# Clock.net
KiCad netlist of a schematic drawn in Altium Designer
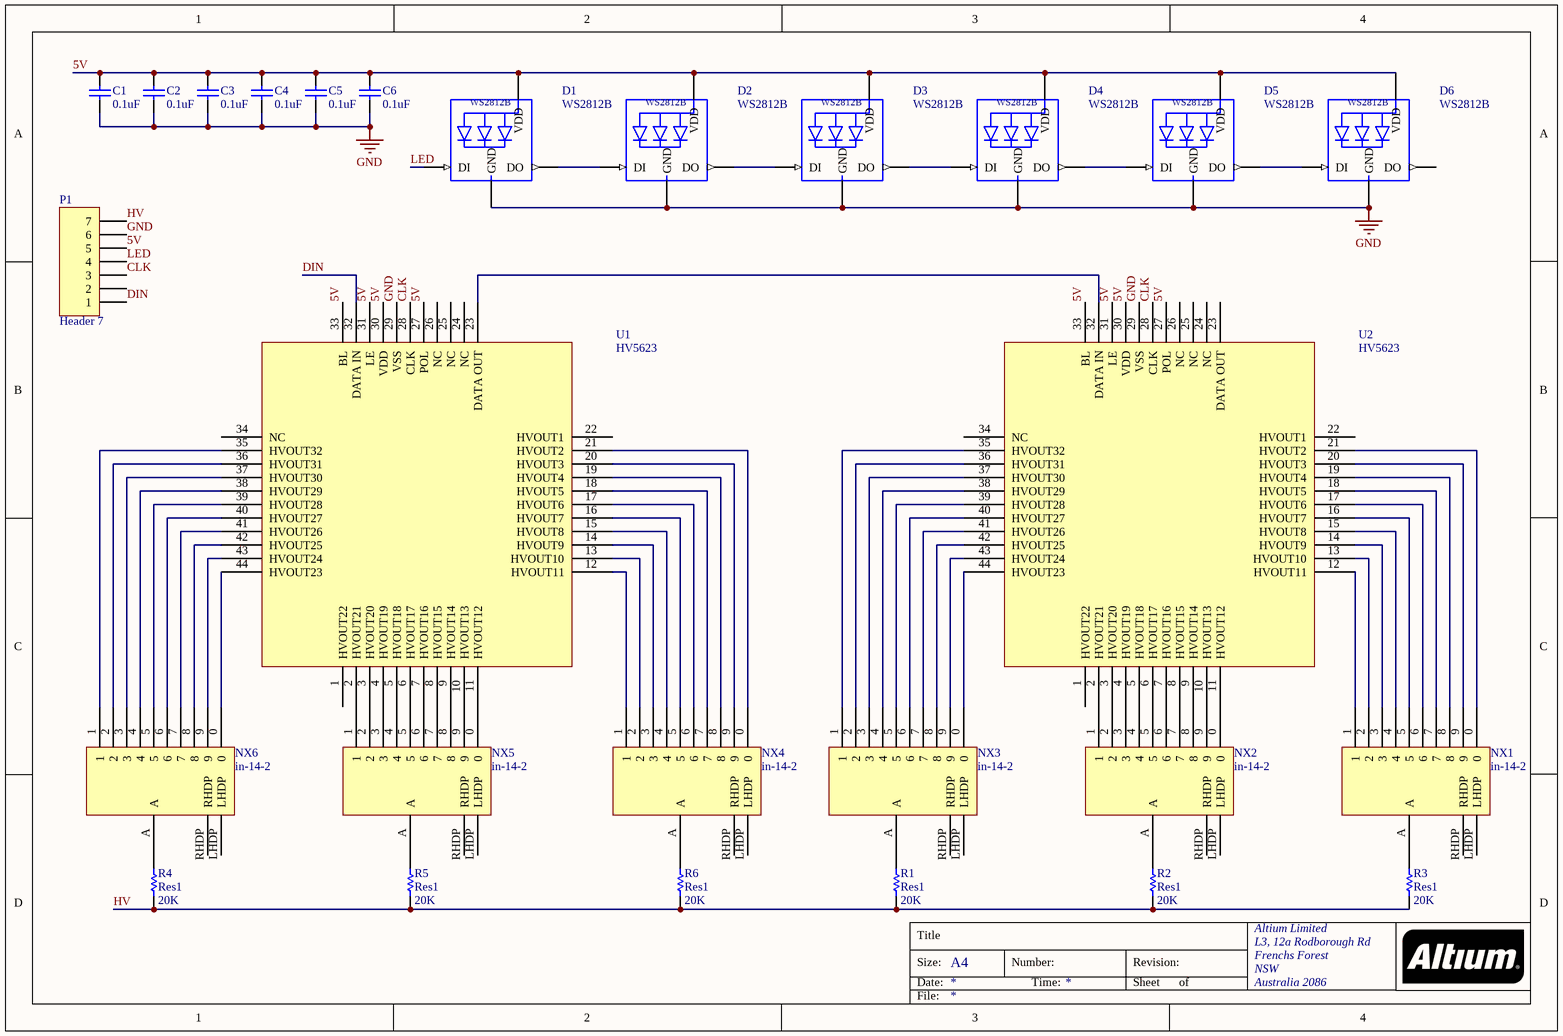
[diagram p0: Clock.SchDoc]

(export (version "E")
  (design (tool "Eeschema 10.0.6"))
  (components
    (comp (ref "C1")
      (value "0.1uF")
      (footprint "1608[0603]")
      (description "Capacitor")
      (fields (field (name "PUBLISHER") "Altium Limited"))
      (libsource (lib "Miscellaneous Devices") (part "Cap"))
    )
    (comp (ref "C2")
      (value "0.1uF")
      (footprint "1608[0603]")
      (description "Capacitor")
      (fields (field (name "PUBLISHER") "Altium Limited"))
      (libsource (lib "Miscellaneous Devices") (part "Cap"))
    )
    (comp (ref "C3")
      (value "0.1uF")
      (footprint "1608[0603]")
      (description "Capacitor")
      (fields (field (name "PUBLISHER") "Altium Limited"))
      (libsource (lib "Miscellaneous Devices") (part "Cap"))
    )
    (comp (ref "C4")
      (value "0.1uF")
      (footprint "1608[0603]")
      (description "Capacitor")
      (fields (field (name "PUBLISHER") "Altium Limited"))
      (libsource (lib "Miscellaneous Devices") (part "Cap"))
    )
    (comp (ref "C5")
      (value "0.1uF")
      (footprint "1608[0603]")
      (description "Capacitor")
      (fields (field (name "PUBLISHER") "Altium Limited"))
      (libsource (lib "Miscellaneous Devices") (part "Cap"))
    )
    (comp (ref "C6")
      (value "0.1uF")
      (footprint "1608[0603]")
      (description "Capacitor")
      (fields (field (name "PUBLISHER") "Altium Limited"))
      (libsource (lib "Miscellaneous Devices") (part "Cap"))
    )
    (comp (ref "D1")
      (value "WS2812B")
      (footprint "WS2812B")
      (description "Raspberry Pi HAT _40 pin_ Wheeled Robotics Kit")
      (fields (field (name "MF") "SparkFun Electronics"))
      (libsource (lib "WS2812B") (part "WS2812B"))
    )
    (comp (ref "D2")
      (value "WS2812B")
      (footprint "WS2812B")
      (description "Raspberry Pi HAT _40 pin_ Wheeled Robotics Kit")
      (fields (field (name "MF") "SparkFun Electronics"))
      (libsource (lib "WS2812B") (part "WS2812B"))
    )
    (comp (ref "D3")
      (value "WS2812B")
      (footprint "WS2812B")
      (description "Raspberry Pi HAT _40 pin_ Wheeled Robotics Kit")
      (fields (field (name "MF") "SparkFun Electronics"))
      (libsource (lib "WS2812B") (part "WS2812B"))
    )
    (comp (ref "D4")
      (value "WS2812B")
      (footprint "WS2812B")
      (description "Raspberry Pi HAT _40 pin_ Wheeled Robotics Kit")
      (fields (field (name "MF") "SparkFun Electronics"))
      (libsource (lib "WS2812B") (part "WS2812B"))
    )
    (comp (ref "D5")
      (value "WS2812B")
      (footprint "WS2812B")
      (description "Raspberry Pi HAT _40 pin_ Wheeled Robotics Kit")
      (fields (field (name "MF") "SparkFun Electronics"))
      (libsource (lib "WS2812B") (part "WS2812B"))
    )
    (comp (ref "D6")
      (value "WS2812B")
      (footprint "WS2812B")
      (description "Raspberry Pi HAT _40 pin_ Wheeled Robotics Kit")
      (fields (field (name "MF") "SparkFun Electronics"))
      (libsource (lib "WS2812B") (part "WS2812B"))
    )
    (comp (ref "NX1")
      (value "in-14-2")
      (footprint "in-14")
      (libsource (lib "CustomComponentsLibrary") (part "in-8"))
    )
    (comp (ref "NX2")
      (value "in-14-2")
      (footprint "in-14")
      (libsource (lib "CustomComponentsLibrary") (part "in-8"))
    )
    (comp (ref "NX3")
      (value "in-14-2")
      (footprint "in-14")
      (libsource (lib "CustomComponentsLibrary") (part "in-8"))
    )
    (comp (ref "NX4")
      (value "in-14-2")
      (footprint "in-14")
      (libsource (lib "CustomComponentsLibrary") (part "in-8"))
    )
    (comp (ref "NX5")
      (value "in-14-2")
      (footprint "in-14")
      (libsource (lib "CustomComponentsLibrary") (part "in-8"))
    )
    (comp (ref "NX6")
      (value "in-14-2")
      (footprint "in-14")
      (libsource (lib "CustomComponentsLibrary") (part "in-8"))
    )
    (comp (ref "P1")
      (value "Header 7")
      (footprint "HDR1X7")
      (description "Header, 7-Pin")
      (fields (field (name "PUBLISHER") "Altium Limited"))
      (libsource (lib "Miscellaneous Connectors") (part "Header 7"))
    )
    (comp (ref "R1")
      (value "Res1")
      (footprint "1608[0603]")
      (description "Resistor")
      (fields (field (name "ALTIUM_VALUE") "20K") (field (name "PUBLISHER") "Altium Limited"))
      (libsource (lib "Miscellaneous Devices") (part "Res1"))
    )
    (comp (ref "R2")
      (value "Res1")
      (footprint "1608[0603]")
      (description "Resistor")
      (fields (field (name "ALTIUM_VALUE") "20K") (field (name "PUBLISHER") "Altium Limited"))
      (libsource (lib "Miscellaneous Devices") (part "Res1"))
    )
    (comp (ref "R3")
      (value "Res1")
      (footprint "1608[0603]")
      (description "Resistor")
      (fields (field (name "ALTIUM_VALUE") "20K") (field (name "PUBLISHER") "Altium Limited"))
      (libsource (lib "Miscellaneous Devices") (part "Res1"))
    )
    (comp (ref "R4")
      (value "Res1")
      (footprint "1608[0603]")
      (description "Resistor")
      (fields (field (name "ALTIUM_VALUE") "20K") (field (name "PUBLISHER") "Altium Limited"))
      (libsource (lib "Miscellaneous Devices") (part "Res1"))
    )
    (comp (ref "R5")
      (value "Res1")
      (footprint "1608[0603]")
      (description "Resistor")
      (fields (field (name "ALTIUM_VALUE") "20K") (field (name "PUBLISHER") "Altium Limited"))
      (libsource (lib "Miscellaneous Devices") (part "Res1"))
    )
    (comp (ref "R6")
      (value "Res1")
      (footprint "1608[0603]")
      (description "Resistor")
      (fields (field (name "ALTIUM_VALUE") "20K") (field (name "PUBLISHER") "Altium Limited"))
      (libsource (lib "Miscellaneous Devices") (part "Res1"))
    )
    (comp (ref "U1")
      (value "HV5623")
      (footprint "Quad44")
      (libsource (lib "CustomComponents") (part "HV5622"))
    )
    (comp (ref "U2")
      (value "HV5623")
      (footprint "Quad44")
      (libsource (lib "CustomComponents") (part "HV5622"))
    )
  )
  (nets
    (net (code "1") (name "/5V") (class "Default")
      (node (ref "C1") (pin "2") (pinfunction "2_2") (pintype "passive"))
      (node (ref "C2") (pin "2") (pinfunction "2_2") (pintype "passive"))
      (node (ref "C3") (pin "2") (pinfunction "2_2") (pintype "passive"))
      (node (ref "C4") (pin "2") (pinfunction "2_2") (pintype "passive"))
      (node (ref "C5") (pin "2") (pinfunction "2_2") (pintype "passive"))
      (node (ref "C6") (pin "2") (pinfunction "2_2") (pintype "passive"))
      (node (ref "D1") (pin "1-VDD") (pinfunction "VDD_1-VDD") (pintype "power_in"))
      (node (ref "D2") (pin "1-VDD") (pinfunction "VDD_1-VDD") (pintype "power_in"))
      (node (ref "D3") (pin "1-VDD") (pinfunction "VDD_1-VDD") (pintype "power_in"))
      (node (ref "D4") (pin "1-VDD") (pinfunction "VDD_1-VDD") (pintype "power_in"))
      (node (ref "D5") (pin "1-VDD") (pinfunction "VDD_1-VDD") (pintype "power_in"))
      (node (ref "D6") (pin "1-VDD") (pinfunction "VDD_1-VDD") (pintype "power_in"))
      (node (ref "P1") (pin "5") (pinfunction "5_5") (pintype "passive"))
      (node (ref "U1") (pin "27") (pinfunction "POL_27") (pintype "passive"))
      (node (ref "U1") (pin "30") (pinfunction "VDD_30") (pintype "passive"))
      (node (ref "U1") (pin "31") (pinfunction "LE_31") (pintype "passive"))
      (node (ref "U1") (pin "33") (pinfunction "BL_33") (pintype "passive"))
      (node (ref "U2") (pin "27") (pinfunction "POL_27") (pintype "passive"))
      (node (ref "U2") (pin "30") (pinfunction "VDD_30") (pintype "passive"))
      (node (ref "U2") (pin "31") (pinfunction "LE_31") (pintype "passive"))
      (node (ref "U2") (pin "33") (pinfunction "BL_33") (pintype "passive"))
    )
    (net (code "2") (name "/CLK") (class "Default")
      (node (ref "P1") (pin "3") (pinfunction "3_3") (pintype "passive"))
      (node (ref "U1") (pin "28") (pinfunction "CLK_28") (pintype "passive"))
      (node (ref "U2") (pin "28") (pinfunction "CLK_28") (pintype "passive"))
    )
    (net (code "3") (name "/DIN") (class "Default")
      (node (ref "P1") (pin "1") (pinfunction "1_1") (pintype "passive"))
      (node (ref "U1") (pin "32") (pinfunction "DATA_IN_32") (pintype "passive"))
    )
    (net (code "4") (name "/HV") (class "Default")
      (node (ref "P1") (pin "7") (pinfunction "7_7") (pintype "passive"))
      (node (ref "R1") (pin "2") (pinfunction "2_2") (pintype "passive"))
      (node (ref "R2") (pin "2") (pinfunction "2_2") (pintype "passive"))
      (node (ref "R3") (pin "2") (pinfunction "2_2") (pintype "passive"))
      (node (ref "R4") (pin "2") (pinfunction "2_2") (pintype "passive"))
      (node (ref "R5") (pin "2") (pinfunction "2_2") (pintype "passive"))
      (node (ref "R6") (pin "2") (pinfunction "2_2") (pintype "passive"))
    )
    (net (code "5") (name "/LED") (class "Default")
      (node (ref "D1") (pin "4-DIN") (pinfunction "DI_4-DIN") (pintype "input"))
      (node (ref "P1") (pin "4") (pinfunction "4_4") (pintype "passive"))
    )
    (net (code "6") (name "GND") (class "Default")
      (node (ref "C1") (pin "1") (pinfunction "1_1") (pintype "passive"))
      (node (ref "C2") (pin "1") (pinfunction "1_1") (pintype "passive"))
      (node (ref "C3") (pin "1") (pinfunction "1_1") (pintype "passive"))
      (node (ref "C4") (pin "1") (pinfunction "1_1") (pintype "passive"))
      (node (ref "C5") (pin "1") (pinfunction "1_1") (pintype "passive"))
      (node (ref "C6") (pin "1") (pinfunction "1_1") (pintype "passive"))
      (node (ref "D1") (pin "3-GND") (pinfunction "GND_3-GND") (pintype "power_in"))
      (node (ref "D2") (pin "3-GND") (pinfunction "GND_3-GND") (pintype "power_in"))
      (node (ref "D3") (pin "3-GND") (pinfunction "GND_3-GND") (pintype "power_in"))
      (node (ref "D4") (pin "3-GND") (pinfunction "GND_3-GND") (pintype "power_in"))
      (node (ref "D5") (pin "3-GND") (pinfunction "GND_3-GND") (pintype "power_in"))
      (node (ref "D6") (pin "3-GND") (pinfunction "GND_3-GND") (pintype "power_in"))
      (node (ref "P1") (pin "6") (pinfunction "6_6") (pintype "passive"))
      (node (ref "U1") (pin "29") (pinfunction "VSS_29") (pintype "passive"))
      (node (ref "U2") (pin "29") (pinfunction "VSS_29") (pintype "passive"))
    )
    (net (code "7") (name "Net-(D1-DO)") (class "Default")
      (node (ref "D1") (pin "2-DOUT") (pinfunction "DO_2-DOUT") (pintype "output"))
      (node (ref "D2") (pin "4-DIN") (pinfunction "DI_4-DIN") (pintype "input"))
    )
    (net (code "8") (name "Net-(D2-DO)") (class "Default")
      (node (ref "D2") (pin "2-DOUT") (pinfunction "DO_2-DOUT") (pintype "output"))
      (node (ref "D3") (pin "4-DIN") (pinfunction "DI_4-DIN") (pintype "input"))
    )
    (net (code "9") (name "Net-(D3-DO)") (class "Default")
      (node (ref "D3") (pin "2-DOUT") (pinfunction "DO_2-DOUT") (pintype "output"))
      (node (ref "D4") (pin "4-DIN") (pinfunction "DI_4-DIN") (pintype "input"))
    )
    (net (code "10") (name "Net-(D4-DO)") (class "Default")
      (node (ref "D4") (pin "2-DOUT") (pinfunction "DO_2-DOUT") (pintype "output"))
      (node (ref "D5") (pin "4-DIN") (pinfunction "DI_4-DIN") (pintype "input"))
    )
    (net (code "11") (name "Net-(D5-DO)") (class "Default")
      (node (ref "D5") (pin "2-DOUT") (pinfunction "DO_2-DOUT") (pintype "output"))
      (node (ref "D6") (pin "4-DIN") (pinfunction "DI_4-DIN") (pintype "input"))
    )
    (net (code "12") (name "Net-(NX1-PadA)") (class "Default")
      (node (ref "NX1") (pin "A") (pinfunction "A_A") (pintype "passive"))
      (node (ref "R3") (pin "1") (pinfunction "1_1") (pintype "passive"))
    )
    (net (code "13") (name "Net-(NX2-PadA)") (class "Default")
      (node (ref "NX2") (pin "A") (pinfunction "A_A") (pintype "passive"))
      (node (ref "R2") (pin "1") (pinfunction "1_1") (pintype "passive"))
    )
    (net (code "14") (name "Net-(NX3-PadA)") (class "Default")
      (node (ref "NX3") (pin "A") (pinfunction "A_A") (pintype "passive"))
      (node (ref "R1") (pin "1") (pinfunction "1_1") (pintype "passive"))
    )
    (net (code "15") (name "Net-(NX4-PadA)") (class "Default")
      (node (ref "NX4") (pin "A") (pinfunction "A_A") (pintype "passive"))
      (node (ref "R6") (pin "1") (pinfunction "1_1") (pintype "passive"))
    )
    (net (code "16") (name "Net-(NX5-PadA)") (class "Default")
      (node (ref "NX5") (pin "A") (pinfunction "A_A") (pintype "passive"))
      (node (ref "R5") (pin "1") (pinfunction "1_1") (pintype "passive"))
    )
    (net (code "17") (name "Net-(NX6-PadA)") (class "Default")
      (node (ref "NX6") (pin "A") (pinfunction "A_A") (pintype "passive"))
      (node (ref "R4") (pin "1") (pinfunction "1_1") (pintype "passive"))
    )
    (net (code "18") (name "Net-(U1-DATA_OUT)") (class "Default")
      (node (ref "U1") (pin "23") (pinfunction "DATA_OUT_23") (pintype "passive"))
      (node (ref "U2") (pin "32") (pinfunction "DATA_IN_32") (pintype "passive"))
    )
    (net (code "19") (name "Net-(U1-HVOUT2)") (class "Default")
      (node (ref "NX4") (pin "0") (pinfunction "0_0") (pintype "passive"))
      (node (ref "U1") (pin "21") (pinfunction "HVOUT2_21") (pintype "passive"))
    )
    (net (code "20") (name "Net-(U1-HVOUT3)") (class "Default")
      (node (ref "NX4") (pin "9") (pinfunction "9_9") (pintype "passive"))
      (node (ref "U1") (pin "20") (pinfunction "HVOUT3_20") (pintype "passive"))
    )
    (net (code "21") (name "Net-(U1-HVOUT4)") (class "Default")
      (node (ref "NX4") (pin "8") (pinfunction "8_8") (pintype "passive"))
      (node (ref "U1") (pin "19") (pinfunction "HVOUT4_19") (pintype "passive"))
    )
    (net (code "22") (name "Net-(U1-HVOUT5)") (class "Default")
      (node (ref "NX4") (pin "7") (pinfunction "7_7") (pintype "passive"))
      (node (ref "U1") (pin "18") (pinfunction "HVOUT5_18") (pintype "passive"))
    )
    (net (code "23") (name "Net-(U1-HVOUT6)") (class "Default")
      (node (ref "NX4") (pin "6") (pinfunction "6_6") (pintype "passive"))
      (node (ref "U1") (pin "17") (pinfunction "HVOUT6_17") (pintype "passive"))
    )
    (net (code "24") (name "Net-(U1-HVOUT7)") (class "Default")
      (node (ref "NX4") (pin "5") (pinfunction "5_5") (pintype "passive"))
      (node (ref "U1") (pin "16") (pinfunction "HVOUT7_16") (pintype "passive"))
    )
    (net (code "25") (name "Net-(U1-HVOUT8)") (class "Default")
      (node (ref "NX4") (pin "4") (pinfunction "4_4") (pintype "passive"))
      (node (ref "U1") (pin "15") (pinfunction "HVOUT8_15") (pintype "passive"))
    )
    (net (code "26") (name "Net-(U1-HVOUT9)") (class "Default")
      (node (ref "NX4") (pin "3") (pinfunction "3_3") (pintype "passive"))
      (node (ref "U1") (pin "14") (pinfunction "HVOUT9_14") (pintype "passive"))
    )
    (net (code "27") (name "Net-(U1-HVOUT10)") (class "Default")
      (node (ref "NX4") (pin "2") (pinfunction "2_2") (pintype "passive"))
      (node (ref "U1") (pin "13") (pinfunction "HVOUT10_13") (pintype "passive"))
    )
    (net (code "28") (name "Net-(U1-HVOUT11)") (class "Default")
      (node (ref "NX4") (pin "1") (pinfunction "1_1") (pintype "passive"))
      (node (ref "U1") (pin "12") (pinfunction "HVOUT11_12") (pintype "passive"))
    )
    (net (code "29") (name "Net-(U1-HVOUT12)") (class "Default")
      (node (ref "NX5") (pin "0") (pinfunction "0_0") (pintype "passive"))
      (node (ref "U1") (pin "11") (pinfunction "HVOUT12_11") (pintype "passive"))
    )
    (net (code "30") (name "Net-(U1-HVOUT13)") (class "Default")
      (node (ref "NX5") (pin "9") (pinfunction "9_9") (pintype "passive"))
      (node (ref "U1") (pin "10") (pinfunction "HVOUT13_10") (pintype "passive"))
    )
    (net (code "31") (name "Net-(U1-HVOUT14)") (class "Default")
      (node (ref "NX5") (pin "8") (pinfunction "8_8") (pintype "passive"))
      (node (ref "U1") (pin "9") (pinfunction "HVOUT14_9") (pintype "passive"))
    )
    (net (code "32") (name "Net-(U1-HVOUT15)") (class "Default")
      (node (ref "NX5") (pin "7") (pinfunction "7_7") (pintype "passive"))
      (node (ref "U1") (pin "8") (pinfunction "HVOUT15_8") (pintype "passive"))
    )
    (net (code "33") (name "Net-(U1-HVOUT16)") (class "Default")
      (node (ref "NX5") (pin "6") (pinfunction "6_6") (pintype "passive"))
      (node (ref "U1") (pin "7") (pinfunction "HVOUT16_7") (pintype "passive"))
    )
    (net (code "34") (name "Net-(U1-HVOUT17)") (class "Default")
      (node (ref "NX5") (pin "5") (pinfunction "5_5") (pintype "passive"))
      (node (ref "U1") (pin "6") (pinfunction "HVOUT17_6") (pintype "passive"))
    )
    (net (code "35") (name "Net-(U1-HVOUT18)") (class "Default")
      (node (ref "NX5") (pin "4") (pinfunction "4_4") (pintype "passive"))
      (node (ref "U1") (pin "5") (pinfunction "HVOUT18_5") (pintype "passive"))
    )
    (net (code "36") (name "Net-(U1-HVOUT19)") (class "Default")
      (node (ref "NX5") (pin "3") (pinfunction "3_3") (pintype "passive"))
      (node (ref "U1") (pin "4") (pinfunction "HVOUT19_4") (pintype "passive"))
    )
    (net (code "37") (name "Net-(U1-HVOUT20)") (class "Default")
      (node (ref "NX5") (pin "2") (pinfunction "2_2") (pintype "passive"))
      (node (ref "U1") (pin "3") (pinfunction "HVOUT20_3") (pintype "passive"))
    )
    (net (code "38") (name "Net-(U1-HVOUT21)") (class "Default")
      (node (ref "NX5") (pin "1") (pinfunction "1_1") (pintype "passive"))
      (node (ref "U1") (pin "2") (pinfunction "HVOUT21_2") (pintype "passive"))
    )
    (net (code "39") (name "Net-(U1-HVOUT23)") (class "Default")
      (node (ref "NX6") (pin "0") (pinfunction "0_0") (pintype "passive"))
      (node (ref "U1") (pin "44") (pinfunction "HVOUT23_44") (pintype "passive"))
    )
    (net (code "40") (name "Net-(U1-HVOUT24)") (class "Default")
      (node (ref "NX6") (pin "9") (pinfunction "9_9") (pintype "passive"))
      (node (ref "U1") (pin "43") (pinfunction "HVOUT24_43") (pintype "passive"))
    )
    (net (code "41") (name "Net-(U1-HVOUT25)") (class "Default")
      (node (ref "NX6") (pin "8") (pinfunction "8_8") (pintype "passive"))
      (node (ref "U1") (pin "42") (pinfunction "HVOUT25_42") (pintype "passive"))
    )
    (net (code "42") (name "Net-(U1-HVOUT26)") (class "Default")
      (node (ref "NX6") (pin "7") (pinfunction "7_7") (pintype "passive"))
      (node (ref "U1") (pin "41") (pinfunction "HVOUT26_41") (pintype "passive"))
    )
    (net (code "43") (name "Net-(U1-HVOUT27)") (class "Default")
      (node (ref "NX6") (pin "6") (pinfunction "6_6") (pintype "passive"))
      (node (ref "U1") (pin "40") (pinfunction "HVOUT27_40") (pintype "passive"))
    )
    (net (code "44") (name "Net-(U1-HVOUT28)") (class "Default")
      (node (ref "NX6") (pin "5") (pinfunction "5_5") (pintype "passive"))
      (node (ref "U1") (pin "39") (pinfunction "HVOUT28_39") (pintype "passive"))
    )
    (net (code "45") (name "Net-(U1-HVOUT29)") (class "Default")
      (node (ref "NX6") (pin "4") (pinfunction "4_4") (pintype "passive"))
      (node (ref "U1") (pin "38") (pinfunction "HVOUT29_38") (pintype "passive"))
    )
    (net (code "46") (name "Net-(U1-HVOUT30)") (class "Default")
      (node (ref "NX6") (pin "3") (pinfunction "3_3") (pintype "passive"))
      (node (ref "U1") (pin "37") (pinfunction "HVOUT30_37") (pintype "passive"))
    )
    (net (code "47") (name "Net-(U1-HVOUT31)") (class "Default")
      (node (ref "NX6") (pin "2") (pinfunction "2_2") (pintype "passive"))
      (node (ref "U1") (pin "36") (pinfunction "HVOUT31_36") (pintype "passive"))
    )
    (net (code "48") (name "Net-(U1-HVOUT32)") (class "Default")
      (node (ref "NX6") (pin "1") (pinfunction "1_1") (pintype "passive"))
      (node (ref "U1") (pin "35") (pinfunction "HVOUT32_35") (pintype "passive"))
    )
    (net (code "49") (name "Net-(U2-HVOUT2)") (class "Default")
      (node (ref "NX1") (pin "0") (pinfunction "0_0") (pintype "passive"))
      (node (ref "U2") (pin "21") (pinfunction "HVOUT2_21") (pintype "passive"))
    )
    (net (code "50") (name "Net-(U2-HVOUT3)") (class "Default")
      (node (ref "NX1") (pin "9") (pinfunction "9_9") (pintype "passive"))
      (node (ref "U2") (pin "20") (pinfunction "HVOUT3_20") (pintype "passive"))
    )
    (net (code "51") (name "Net-(U2-HVOUT4)") (class "Default")
      (node (ref "NX1") (pin "8") (pinfunction "8_8") (pintype "passive"))
      (node (ref "U2") (pin "19") (pinfunction "HVOUT4_19") (pintype "passive"))
    )
    (net (code "52") (name "Net-(U2-HVOUT5)") (class "Default")
      (node (ref "NX1") (pin "7") (pinfunction "7_7") (pintype "passive"))
      (node (ref "U2") (pin "18") (pinfunction "HVOUT5_18") (pintype "passive"))
    )
    (net (code "53") (name "Net-(U2-HVOUT6)") (class "Default")
      (node (ref "NX1") (pin "6") (pinfunction "6_6") (pintype "passive"))
      (node (ref "U2") (pin "17") (pinfunction "HVOUT6_17") (pintype "passive"))
    )
    (net (code "54") (name "Net-(U2-HVOUT7)") (class "Default")
      (node (ref "NX1") (pin "5") (pinfunction "5_5") (pintype "passive"))
      (node (ref "U2") (pin "16") (pinfunction "HVOUT7_16") (pintype "passive"))
    )
    (net (code "55") (name "Net-(U2-HVOUT8)") (class "Default")
      (node (ref "NX1") (pin "4") (pinfunction "4_4") (pintype "passive"))
      (node (ref "U2") (pin "15") (pinfunction "HVOUT8_15") (pintype "passive"))
    )
    (net (code "56") (name "Net-(U2-HVOUT9)") (class "Default")
      (node (ref "NX1") (pin "3") (pinfunction "3_3") (pintype "passive"))
      (node (ref "U2") (pin "14") (pinfunction "HVOUT9_14") (pintype "passive"))
    )
    (net (code "57") (name "Net-(U2-HVOUT10)") (class "Default")
      (node (ref "NX1") (pin "2") (pinfunction "2_2") (pintype "passive"))
      (node (ref "U2") (pin "13") (pinfunction "HVOUT10_13") (pintype "passive"))
    )
    (net (code "58") (name "Net-(U2-HVOUT11)") (class "Default")
      (node (ref "NX1") (pin "1") (pinfunction "1_1") (pintype "passive"))
      (node (ref "U2") (pin "12") (pinfunction "HVOUT11_12") (pintype "passive"))
    )
    (net (code "59") (name "Net-(U2-HVOUT12)") (class "Default")
      (node (ref "NX2") (pin "0") (pinfunction "0_0") (pintype "passive"))
      (node (ref "U2") (pin "11") (pinfunction "HVOUT12_11") (pintype "passive"))
    )
    (net (code "60") (name "Net-(U2-HVOUT13)") (class "Default")
      (node (ref "NX2") (pin "9") (pinfunction "9_9") (pintype "passive"))
      (node (ref "U2") (pin "10") (pinfunction "HVOUT13_10") (pintype "passive"))
    )
    (net (code "61") (name "Net-(U2-HVOUT14)") (class "Default")
      (node (ref "NX2") (pin "8") (pinfunction "8_8") (pintype "passive"))
      (node (ref "U2") (pin "9") (pinfunction "HVOUT14_9") (pintype "passive"))
    )
    (net (code "62") (name "Net-(U2-HVOUT15)") (class "Default")
      (node (ref "NX2") (pin "7") (pinfunction "7_7") (pintype "passive"))
      (node (ref "U2") (pin "8") (pinfunction "HVOUT15_8") (pintype "passive"))
    )
    (net (code "63") (name "Net-(U2-HVOUT16)") (class "Default")
      (node (ref "NX2") (pin "6") (pinfunction "6_6") (pintype "passive"))
      (node (ref "U2") (pin "7") (pinfunction "HVOUT16_7") (pintype "passive"))
    )
    (net (code "64") (name "Net-(U2-HVOUT17)") (class "Default")
      (node (ref "NX2") (pin "5") (pinfunction "5_5") (pintype "passive"))
      (node (ref "U2") (pin "6") (pinfunction "HVOUT17_6") (pintype "passive"))
    )
    (net (code "65") (name "Net-(U2-HVOUT18)") (class "Default")
      (node (ref "NX2") (pin "4") (pinfunction "4_4") (pintype "passive"))
      (node (ref "U2") (pin "5") (pinfunction "HVOUT18_5") (pintype "passive"))
    )
    (net (code "66") (name "Net-(U2-HVOUT19)") (class "Default")
      (node (ref "NX2") (pin "3") (pinfunction "3_3") (pintype "passive"))
      (node (ref "U2") (pin "4") (pinfunction "HVOUT19_4") (pintype "passive"))
    )
    (net (code "67") (name "Net-(U2-HVOUT20)") (class "Default")
      (node (ref "NX2") (pin "2") (pinfunction "2_2") (pintype "passive"))
      (node (ref "U2") (pin "3") (pinfunction "HVOUT20_3") (pintype "passive"))
    )
    (net (code "68") (name "Net-(U2-HVOUT21)") (class "Default")
      (node (ref "NX2") (pin "1") (pinfunction "1_1") (pintype "passive"))
      (node (ref "U2") (pin "2") (pinfunction "HVOUT21_2") (pintype "passive"))
    )
    (net (code "69") (name "Net-(U2-HVOUT23)") (class "Default")
      (node (ref "NX3") (pin "0") (pinfunction "0_0") (pintype "passive"))
      (node (ref "U2") (pin "44") (pinfunction "HVOUT23_44") (pintype "passive"))
    )
    (net (code "70") (name "Net-(U2-HVOUT24)") (class "Default")
      (node (ref "NX3") (pin "9") (pinfunction "9_9") (pintype "passive"))
      (node (ref "U2") (pin "43") (pinfunction "HVOUT24_43") (pintype "passive"))
    )
    (net (code "71") (name "Net-(U2-HVOUT25)") (class "Default")
      (node (ref "NX3") (pin "8") (pinfunction "8_8") (pintype "passive"))
      (node (ref "U2") (pin "42") (pinfunction "HVOUT25_42") (pintype "passive"))
    )
    (net (code "72") (name "Net-(U2-HVOUT26)") (class "Default")
      (node (ref "NX3") (pin "7") (pinfunction "7_7") (pintype "passive"))
      (node (ref "U2") (pin "41") (pinfunction "HVOUT26_41") (pintype "passive"))
    )
    (net (code "73") (name "Net-(U2-HVOUT27)") (class "Default")
      (node (ref "NX3") (pin "6") (pinfunction "6_6") (pintype "passive"))
      (node (ref "U2") (pin "40") (pinfunction "HVOUT27_40") (pintype "passive"))
    )
    (net (code "74") (name "Net-(U2-HVOUT28)") (class "Default")
      (node (ref "NX3") (pin "5") (pinfunction "5_5") (pintype "passive"))
      (node (ref "U2") (pin "39") (pinfunction "HVOUT28_39") (pintype "passive"))
    )
    (net (code "75") (name "Net-(U2-HVOUT29)") (class "Default")
      (node (ref "NX3") (pin "4") (pinfunction "4_4") (pintype "passive"))
      (node (ref "U2") (pin "38") (pinfunction "HVOUT29_38") (pintype "passive"))
    )
    (net (code "76") (name "Net-(U2-HVOUT30)") (class "Default")
      (node (ref "NX3") (pin "3") (pinfunction "3_3") (pintype "passive"))
      (node (ref "U2") (pin "37") (pinfunction "HVOUT30_37") (pintype "passive"))
    )
    (net (code "77") (name "Net-(U2-HVOUT31)") (class "Default")
      (node (ref "NX3") (pin "2") (pinfunction "2_2") (pintype "passive"))
      (node (ref "U2") (pin "36") (pinfunction "HVOUT31_36") (pintype "passive"))
    )
    (net (code "78") (name "Net-(U2-HVOUT32)") (class "Default")
      (node (ref "NX3") (pin "1") (pinfunction "1_1") (pintype "passive"))
      (node (ref "U2") (pin "35") (pinfunction "HVOUT32_35") (pintype "passive"))
    )
    (net (code "79") (name "unconnected-(D6-DO-Pad2-DOUT)") (class "Default")
      (node (ref "D6") (pin "2-DOUT") (pinfunction "DO_2-DOUT") (pintype "output"))
    )
    (net (code "80") (name "unconnected-(NX1-PadLHDP)") (class "Default")
      (node (ref "NX1") (pin "LHDP") (pinfunction "LHDP_LHDP") (pintype "passive"))
    )
    (net (code "81") (name "unconnected-(NX1-PadRHDP)") (class "Default")
      (node (ref "NX1") (pin "RHDP") (pinfunction "RHDP_RHDP") (pintype "passive"))
    )
    (net (code "82") (name "unconnected-(NX2-PadLHDP)") (class "Default")
      (node (ref "NX2") (pin "LHDP") (pinfunction "LHDP_LHDP") (pintype "passive"))
    )
    (net (code "83") (name "unconnected-(NX2-PadRHDP)") (class "Default")
      (node (ref "NX2") (pin "RHDP") (pinfunction "RHDP_RHDP") (pintype "passive"))
    )
    (net (code "84") (name "unconnected-(NX3-PadLHDP)") (class "Default")
      (node (ref "NX3") (pin "LHDP") (pinfunction "LHDP_LHDP") (pintype "passive"))
    )
    (net (code "85") (name "unconnected-(NX3-PadRHDP)") (class "Default")
      (node (ref "NX3") (pin "RHDP") (pinfunction "RHDP_RHDP") (pintype "passive"))
    )
    (net (code "86") (name "unconnected-(NX4-PadLHDP)") (class "Default")
      (node (ref "NX4") (pin "LHDP") (pinfunction "LHDP_LHDP") (pintype "passive"))
    )
    (net (code "87") (name "unconnected-(NX4-PadRHDP)") (class "Default")
      (node (ref "NX4") (pin "RHDP") (pinfunction "RHDP_RHDP") (pintype "passive"))
    )
    (net (code "88") (name "unconnected-(NX5-PadLHDP)") (class "Default")
      (node (ref "NX5") (pin "LHDP") (pinfunction "LHDP_LHDP") (pintype "passive"))
    )
    (net (code "89") (name "unconnected-(NX5-PadRHDP)") (class "Default")
      (node (ref "NX5") (pin "RHDP") (pinfunction "RHDP_RHDP") (pintype "passive"))
    )
    (net (code "90") (name "unconnected-(NX6-PadLHDP)") (class "Default")
      (node (ref "NX6") (pin "LHDP") (pinfunction "LHDP_LHDP") (pintype "passive"))
    )
    (net (code "91") (name "unconnected-(NX6-PadRHDP)") (class "Default")
      (node (ref "NX6") (pin "RHDP") (pinfunction "RHDP_RHDP") (pintype "passive"))
    )
    (net (code "92") (name "unconnected-(P1-Pad2)") (class "Default")
      (node (ref "P1") (pin "2") (pinfunction "2_2") (pintype "passive"))
    )
    (net (code "93") (name "unconnected-(U1-HVOUT1-Pad22)") (class "Default")
      (node (ref "U1") (pin "22") (pinfunction "HVOUT1_22") (pintype "passive"))
    )
    (net (code "94") (name "unconnected-(U1-HVOUT22-Pad1)") (class "Default")
      (node (ref "U1") (pin "1") (pinfunction "HVOUT22_1") (pintype "passive"))
    )
    (net (code "95") (name "unconnected-(U1-NC-Pad24)") (class "Default")
      (node (ref "U1") (pin "24") (pinfunction "NC_24") (pintype "passive"))
    )
    (net (code "96") (name "unconnected-(U1-NC-Pad25)") (class "Default")
      (node (ref "U1") (pin "25") (pinfunction "NC_25") (pintype "passive"))
    )
    (net (code "97") (name "unconnected-(U1-NC-Pad26)") (class "Default")
      (node (ref "U1") (pin "26") (pinfunction "NC_26") (pintype "passive"))
    )
    (net (code "98") (name "unconnected-(U1-NC-Pad34)") (class "Default")
      (node (ref "U1") (pin "34") (pinfunction "NC_34") (pintype "passive"))
    )
    (net (code "99") (name "unconnected-(U2-DATA_OUT-Pad23)") (class "Default")
      (node (ref "U2") (pin "23") (pinfunction "DATA_OUT_23") (pintype "passive"))
    )
    (net (code "100") (name "unconnected-(U2-HVOUT1-Pad22)") (class "Default")
      (node (ref "U2") (pin "22") (pinfunction "HVOUT1_22") (pintype "passive"))
    )
    (net (code "101") (name "unconnected-(U2-HVOUT22-Pad1)") (class "Default")
      (node (ref "U2") (pin "1") (pinfunction "HVOUT22_1") (pintype "passive"))
    )
    (net (code "102") (name "unconnected-(U2-NC-Pad24)") (class "Default")
      (node (ref "U2") (pin "24") (pinfunction "NC_24") (pintype "passive"))
    )
    (net (code "103") (name "unconnected-(U2-NC-Pad25)") (class "Default")
      (node (ref "U2") (pin "25") (pinfunction "NC_25") (pintype "passive"))
    )
    (net (code "104") (name "unconnected-(U2-NC-Pad26)") (class "Default")
      (node (ref "U2") (pin "26") (pinfunction "NC_26") (pintype "passive"))
    )
    (net (code "105") (name "unconnected-(U2-NC-Pad34)") (class "Default")
      (node (ref "U2") (pin "34") (pinfunction "NC_34") (pintype "passive"))
    )
  )
)
